# PCB-BC-BI.net
KiCad netlist of a schematic drawn in EAGLE
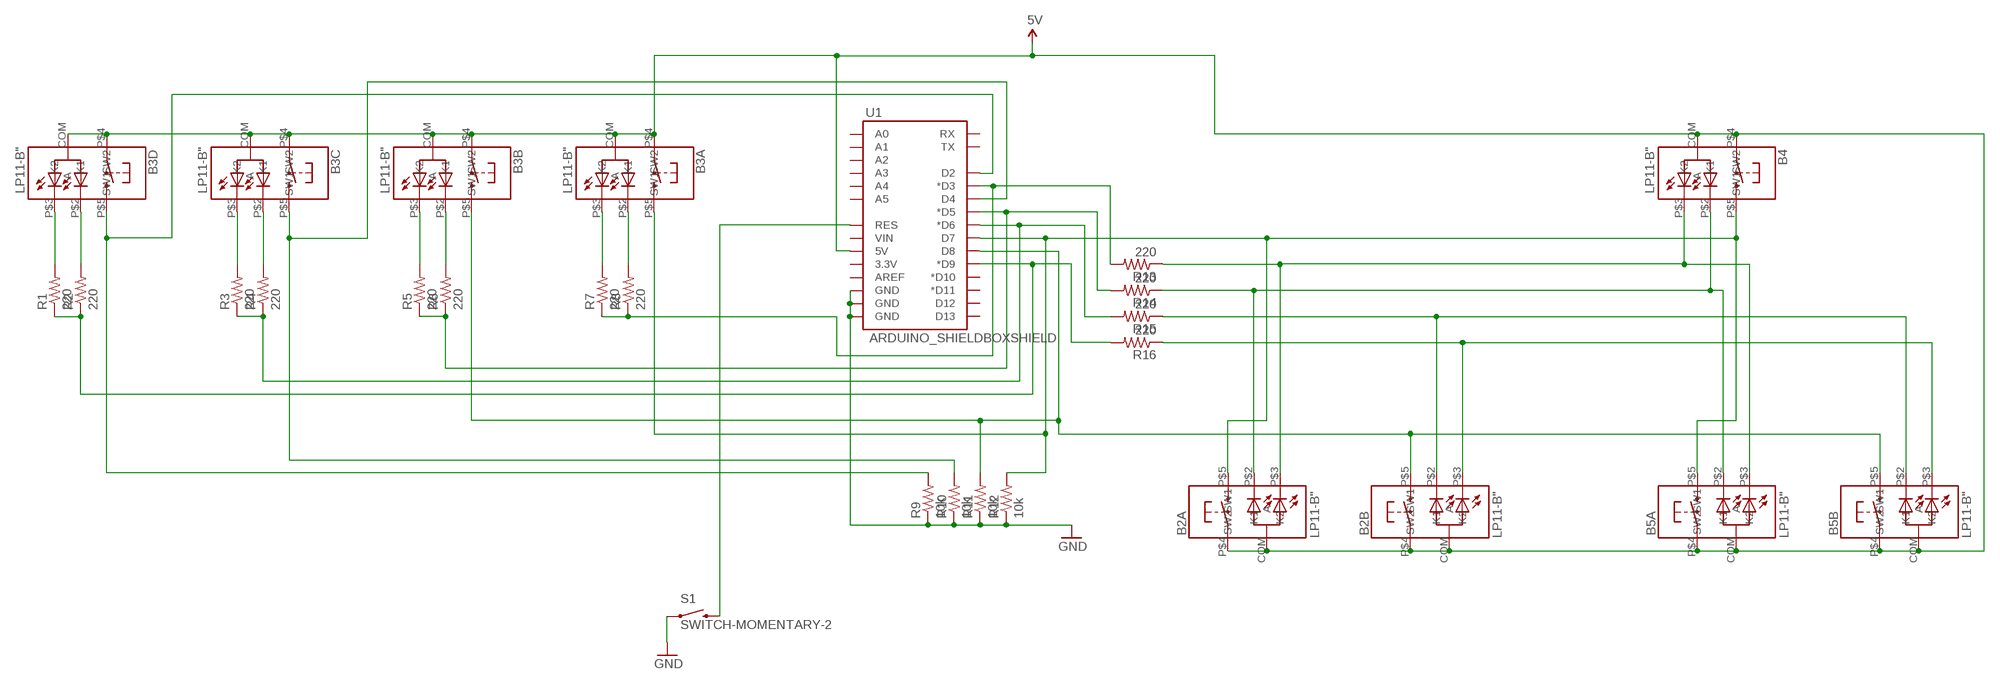
[diagram p0: schematic, sheet 1]

(export (version "E")
  (design (tool "Eeschema 10.0.6"))
  (components
    (comp (ref "B2A")
      (value "LP11-B\"")
      (footprint "eagle-import:LP11")
      (libsource (lib "eagle-import") (part "LP11-B{dblquote}"))
    )
    (comp (ref "B2B")
      (value "LP11-B\"")
      (footprint "eagle-import:LP11")
      (libsource (lib "eagle-import") (part "LP11-B{dblquote}"))
    )
    (comp (ref "B3A")
      (value "LP11-B\"")
      (footprint "eagle-import:LP11")
      (libsource (lib "eagle-import") (part "LP11-B{dblquote}"))
    )
    (comp (ref "B3B")
      (value "LP11-B\"")
      (footprint "eagle-import:LP11")
      (libsource (lib "eagle-import") (part "LP11-B{dblquote}"))
    )
    (comp (ref "B3C")
      (value "LP11-B\"")
      (footprint "eagle-import:LP11")
      (libsource (lib "eagle-import") (part "LP11-B{dblquote}"))
    )
    (comp (ref "B3D")
      (value "LP11-B\"")
      (footprint "eagle-import:LP11")
      (libsource (lib "eagle-import") (part "LP11-B{dblquote}"))
    )
    (comp (ref "B4")
      (value "LP11-B\"")
      (footprint "eagle-import:LP11")
      (libsource (lib "eagle-import") (part "LP11-B{dblquote}"))
    )
    (comp (ref "B5A")
      (value "LP11-B\"")
      (footprint "eagle-import:LP11")
      (libsource (lib "eagle-import") (part "LP11-B{dblquote}"))
    )
    (comp (ref "B5B")
      (value "LP11-B\"")
      (footprint "eagle-import:LP11")
      (libsource (lib "eagle-import") (part "LP11-B{dblquote}"))
    )
    (comp (ref "R1")
      (value "220")
      (footprint "eagle-import:0603-RES")
      (libsource (lib "eagle-import") (part "RESISTOR0603-RES"))
    )
    (comp (ref "R2")
      (value "220")
      (footprint "eagle-import:0603-RES")
      (libsource (lib "eagle-import") (part "RESISTOR0603-RES"))
    )
    (comp (ref "R3")
      (value "220")
      (footprint "eagle-import:0603-RES")
      (libsource (lib "eagle-import") (part "RESISTOR0603-RES"))
    )
    (comp (ref "R4")
      (value "220")
      (footprint "eagle-import:0603-RES")
      (libsource (lib "eagle-import") (part "RESISTOR0603-RES"))
    )
    (comp (ref "R5")
      (value "220")
      (footprint "eagle-import:0603-RES")
      (libsource (lib "eagle-import") (part "RESISTOR0603-RES"))
    )
    (comp (ref "R6")
      (value "220")
      (footprint "eagle-import:0603-RES")
      (libsource (lib "eagle-import") (part "RESISTOR0603-RES"))
    )
    (comp (ref "R7")
      (value "220")
      (footprint "eagle-import:0603-RES")
      (libsource (lib "eagle-import") (part "RESISTOR0603-RES"))
    )
    (comp (ref "R8")
      (value "220")
      (footprint "eagle-import:0603-RES")
      (libsource (lib "eagle-import") (part "RESISTOR0603-RES"))
    )
    (comp (ref "R9")
      (value "10k")
      (footprint "eagle-import:0603-RES")
      (libsource (lib "eagle-import") (part "RESISTOR0603-RES"))
    )
    (comp (ref "R10")
      (value "10k")
      (footprint "eagle-import:0603-RES")
      (libsource (lib "eagle-import") (part "RESISTOR0603-RES"))
    )
    (comp (ref "R11")
      (value "10k")
      (footprint "eagle-import:0603-RES")
      (libsource (lib "eagle-import") (part "RESISTOR0603-RES"))
    )
    (comp (ref "R12")
      (value "10k")
      (footprint "eagle-import:0603-RES")
      (libsource (lib "eagle-import") (part "RESISTOR0603-RES"))
    )
    (comp (ref "R13")
      (value "220")
      (footprint "eagle-import:0603-RES")
      (libsource (lib "eagle-import") (part "RESISTOR0603-RES"))
    )
    (comp (ref "R14")
      (value "220")
      (footprint "eagle-import:0603-RES")
      (libsource (lib "eagle-import") (part "RESISTOR0603-RES"))
    )
    (comp (ref "R15")
      (value "220")
      (footprint "eagle-import:0603-RES")
      (libsource (lib "eagle-import") (part "RESISTOR0603-RES"))
    )
    (comp (ref "R16")
      (value "220")
      (footprint "eagle-import:0603-RES")
      (libsource (lib "eagle-import") (part "RESISTOR0603-RES"))
    )
    (comp (ref "S1")
      (value "SWITCH-MOMENTARY-2")
      (footprint "eagle-import:TACTILE_SWITCH_TALL")
      (libsource (lib "eagle-import") (part "SWITCH-MOMENTARY-2"))
    )
    (comp (ref "U1")
      (value "ARDUINO_SHIELDBOXSHIELD")
      (footprint "eagle-import:ARDUINO_BOXSHIELD")
      (libsource (lib "eagle-import") (part "ARDUINO_SHIELDBOXSHIELD"))
    )
  )
  (nets
    (net (code "1") (name "5V") (class "Default")
      (node (ref "B2A") (pin "COM") (pinfunction "A_COM") (pintype "bidirectional"))
      (node (ref "B2A") (pin "P$4") (pinfunction "SW1_P$4") (pintype "bidirectional"))
      (node (ref "B2B") (pin "COM") (pinfunction "A_COM") (pintype "bidirectional"))
      (node (ref "B2B") (pin "P$4") (pinfunction "SW1_P$4") (pintype "bidirectional"))
      (node (ref "B3A") (pin "COM") (pinfunction "A_COM") (pintype "bidirectional"))
      (node (ref "B3A") (pin "P$4") (pinfunction "SW1_P$4") (pintype "bidirectional"))
      (node (ref "B3B") (pin "COM") (pinfunction "A_COM") (pintype "bidirectional"))
      (node (ref "B3B") (pin "P$4") (pinfunction "SW1_P$4") (pintype "bidirectional"))
      (node (ref "B3C") (pin "COM") (pinfunction "A_COM") (pintype "bidirectional"))
      (node (ref "B3C") (pin "P$4") (pinfunction "SW1_P$4") (pintype "bidirectional"))
      (node (ref "B3D") (pin "COM") (pinfunction "A_COM") (pintype "bidirectional"))
      (node (ref "B3D") (pin "P$4") (pinfunction "SW1_P$4") (pintype "bidirectional"))
      (node (ref "B4") (pin "COM") (pinfunction "A_COM") (pintype "bidirectional"))
      (node (ref "B4") (pin "P$4") (pinfunction "SW1_P$4") (pintype "bidirectional"))
      (node (ref "B5A") (pin "COM") (pinfunction "A_COM") (pintype "bidirectional"))
      (node (ref "B5A") (pin "P$4") (pinfunction "SW1_P$4") (pintype "bidirectional"))
      (node (ref "B5B") (pin "COM") (pinfunction "A_COM") (pintype "bidirectional"))
      (node (ref "B5B") (pin "P$4") (pinfunction "SW1_P$4") (pintype "bidirectional"))
      (node (ref "U1") (pin "5V@0") (pinfunction "5V_5V@0") (pintype "bidirectional"))
    )
    (net (code "2") (name "GND") (class "Default")
      (node (ref "R10") (pin "1") (pinfunction "1_1") (pintype "passive"))
      (node (ref "R11") (pin "1") (pinfunction "1_1") (pintype "passive"))
      (node (ref "R12") (pin "1") (pinfunction "1_1") (pintype "passive"))
      (node (ref "R9") (pin "1") (pinfunction "1_1") (pintype "passive"))
      (node (ref "S1") (pin "A2") (pinfunction "1_A2") (pintype "passive"))
      (node (ref "U1") (pin "GND@0") (pinfunction "GND_GND@0") (pintype "bidirectional"))
      (node (ref "U1") (pin "GND@1") (pinfunction "GND_GND@1") (pintype "bidirectional"))
      (node (ref "U1") (pin "GND@4") (pinfunction "GND_GND@4") (pintype "bidirectional"))
    )
    (net (code "3") (name "Net-(B2A-K1)") (class "Default")
      (node (ref "B2A") (pin "P$2") (pinfunction "K1_P$2") (pintype "bidirectional"))
      (node (ref "B4") (pin "P$2") (pinfunction "K1_P$2") (pintype "bidirectional"))
      (node (ref "B5A") (pin "P$2") (pinfunction "K1_P$2") (pintype "bidirectional"))
      (node (ref "R14") (pin "1") (pinfunction "1_1") (pintype "passive"))
    )
    (net (code "4") (name "Net-(B2A-K2)") (class "Default")
      (node (ref "B2A") (pin "P$3") (pinfunction "K2_P$3") (pintype "bidirectional"))
      (node (ref "B4") (pin "P$3") (pinfunction "K2_P$3") (pintype "bidirectional"))
      (node (ref "B5A") (pin "P$3") (pinfunction "K2_P$3") (pintype "bidirectional"))
      (node (ref "R13") (pin "1") (pinfunction "1_1") (pintype "passive"))
    )
    (net (code "5") (name "Net-(B2A-SW2)") (class "Default")
      (node (ref "B2A") (pin "P$5") (pinfunction "SW2_P$5") (pintype "bidirectional"))
      (node (ref "B3A") (pin "P$5") (pinfunction "SW2_P$5") (pintype "bidirectional"))
      (node (ref "B4") (pin "P$5") (pinfunction "SW2_P$5") (pintype "bidirectional"))
      (node (ref "B5A") (pin "P$5") (pinfunction "SW2_P$5") (pintype "bidirectional"))
      (node (ref "R12") (pin "2") (pinfunction "2_2") (pintype "passive"))
      (node (ref "U1") (pin "7") (pinfunction "D7_7") (pintype "bidirectional"))
    )
    (net (code "6") (name "Net-(B2B-K1)") (class "Default")
      (node (ref "B2B") (pin "P$2") (pinfunction "K1_P$2") (pintype "bidirectional"))
      (node (ref "B5B") (pin "P$2") (pinfunction "K1_P$2") (pintype "bidirectional"))
      (node (ref "R15") (pin "1") (pinfunction "1_1") (pintype "passive"))
    )
    (net (code "7") (name "Net-(B2B-K2)") (class "Default")
      (node (ref "B2B") (pin "P$3") (pinfunction "K2_P$3") (pintype "bidirectional"))
      (node (ref "B5B") (pin "P$3") (pinfunction "K2_P$3") (pintype "bidirectional"))
      (node (ref "R16") (pin "1") (pinfunction "1_1") (pintype "passive"))
    )
    (net (code "8") (name "Net-(B2B-SW2)") (class "Default")
      (node (ref "B2B") (pin "P$5") (pinfunction "SW2_P$5") (pintype "bidirectional"))
      (node (ref "B3B") (pin "P$5") (pinfunction "SW2_P$5") (pintype "bidirectional"))
      (node (ref "B5B") (pin "P$5") (pinfunction "SW2_P$5") (pintype "bidirectional"))
      (node (ref "R11") (pin "2") (pinfunction "2_2") (pintype "passive"))
      (node (ref "U1") (pin "8") (pinfunction "D8_8") (pintype "bidirectional"))
    )
    (net (code "9") (name "Net-(B3A-K1)") (class "Default")
      (node (ref "B3A") (pin "P$2") (pinfunction "K1_P$2") (pintype "bidirectional"))
      (node (ref "R8") (pin "2") (pinfunction "2_2") (pintype "passive"))
    )
    (net (code "10") (name "Net-(B3A-K2)") (class "Default")
      (node (ref "B3A") (pin "P$3") (pinfunction "K2_P$3") (pintype "bidirectional"))
      (node (ref "R7") (pin "2") (pinfunction "2_2") (pintype "passive"))
    )
    (net (code "11") (name "Net-(B3B-K1)") (class "Default")
      (node (ref "B3B") (pin "P$2") (pinfunction "K1_P$2") (pintype "bidirectional"))
      (node (ref "R6") (pin "2") (pinfunction "2_2") (pintype "passive"))
    )
    (net (code "12") (name "Net-(B3B-K2)") (class "Default")
      (node (ref "B3B") (pin "P$3") (pinfunction "K2_P$3") (pintype "bidirectional"))
      (node (ref "R5") (pin "2") (pinfunction "2_2") (pintype "passive"))
    )
    (net (code "13") (name "Net-(B3C-K1)") (class "Default")
      (node (ref "B3C") (pin "P$2") (pinfunction "K1_P$2") (pintype "bidirectional"))
      (node (ref "R4") (pin "2") (pinfunction "2_2") (pintype "passive"))
    )
    (net (code "14") (name "Net-(B3C-K2)") (class "Default")
      (node (ref "B3C") (pin "P$3") (pinfunction "K2_P$3") (pintype "bidirectional"))
      (node (ref "R3") (pin "2") (pinfunction "2_2") (pintype "passive"))
    )
    (net (code "15") (name "Net-(B3C-SW2)") (class "Default")
      (node (ref "B3C") (pin "P$5") (pinfunction "SW2_P$5") (pintype "bidirectional"))
      (node (ref "R10") (pin "2") (pinfunction "2_2") (pintype "passive"))
      (node (ref "U1") (pin "4") (pinfunction "D4_4") (pintype "bidirectional"))
    )
    (net (code "16") (name "Net-(B3D-K1)") (class "Default")
      (node (ref "B3D") (pin "P$2") (pinfunction "K1_P$2") (pintype "bidirectional"))
      (node (ref "R2") (pin "2") (pinfunction "2_2") (pintype "passive"))
    )
    (net (code "17") (name "Net-(B3D-K2)") (class "Default")
      (node (ref "B3D") (pin "P$3") (pinfunction "K2_P$3") (pintype "bidirectional"))
      (node (ref "R1") (pin "2") (pinfunction "2_2") (pintype "passive"))
    )
    (net (code "18") (name "Net-(B3D-SW2)") (class "Default")
      (node (ref "B3D") (pin "P$5") (pinfunction "SW2_P$5") (pintype "bidirectional"))
      (node (ref "R9") (pin "2") (pinfunction "2_2") (pintype "passive"))
      (node (ref "U1") (pin "2") (pinfunction "D2_2") (pintype "bidirectional"))
    )
    (net (code "19") (name "Net-(S1-2)") (class "Default")
      (node (ref "S1") (pin "B2") (pinfunction "2_B2") (pintype "passive"))
      (node (ref "U1") (pin "RESET") (pinfunction "RES_RESET") (pintype "bidirectional"))
    )
    (net (code "20") (name "Net-(U1-*D3)") (class "Default")
      (node (ref "R13") (pin "2") (pinfunction "2_2") (pintype "passive"))
      (node (ref "R7") (pin "1") (pinfunction "1_1") (pintype "passive"))
      (node (ref "R8") (pin "1") (pinfunction "1_1") (pintype "passive"))
      (node (ref "U1") (pin "3") (pinfunction "*D3_3") (pintype "bidirectional"))
    )
    (net (code "21") (name "Net-(U1-*D5)") (class "Default")
      (node (ref "R14") (pin "2") (pinfunction "2_2") (pintype "passive"))
      (node (ref "R5") (pin "1") (pinfunction "1_1") (pintype "passive"))
      (node (ref "R6") (pin "1") (pinfunction "1_1") (pintype "passive"))
      (node (ref "U1") (pin "5") (pinfunction "*D5_5") (pintype "bidirectional"))
    )
    (net (code "22") (name "Net-(U1-*D6)") (class "Default")
      (node (ref "R15") (pin "2") (pinfunction "2_2") (pintype "passive"))
      (node (ref "R3") (pin "1") (pinfunction "1_1") (pintype "passive"))
      (node (ref "R4") (pin "1") (pinfunction "1_1") (pintype "passive"))
      (node (ref "U1") (pin "6") (pinfunction "*D6_6") (pintype "bidirectional"))
    )
    (net (code "23") (name "Net-(U1-*D9)") (class "Default")
      (node (ref "R1") (pin "1") (pinfunction "1_1") (pintype "passive"))
      (node (ref "R16") (pin "2") (pinfunction "2_2") (pintype "passive"))
      (node (ref "R2") (pin "1") (pinfunction "1_1") (pintype "passive"))
      (node (ref "U1") (pin "9") (pinfunction "*D9_9") (pintype "bidirectional"))
    )
    (net (code "24") (name "unconnected-(U1-*D10-Pad10)") (class "Default")
      (node (ref "U1") (pin "10") (pinfunction "*D10_10") (pintype "bidirectional"))
    )
    (net (code "25") (name "unconnected-(U1-*D11-Pad11)") (class "Default")
      (node (ref "U1") (pin "11") (pinfunction "*D11_11") (pintype "bidirectional"))
    )
    (net (code "26") (name "unconnected-(U1-D12-Pad12)") (class "Default")
      (node (ref "U1") (pin "12") (pinfunction "D12_12") (pintype "bidirectional"))
    )
    (net (code "27") (name "unconnected-(U1-D13-Pad13)") (class "Default")
      (node (ref "U1") (pin "13") (pinfunction "D13_13") (pintype "bidirectional"))
    )
    (net (code "28") (name "unconnected-(U1-Pad3.3V)") (class "Default")
      (node (ref "U1") (pin "3.3V") (pinfunction "3.3V_3.3V") (pintype "bidirectional"))
    )
    (net (code "29") (name "unconnected-(U1-PadA0)") (class "Default")
      (node (ref "U1") (pin "A0") (pinfunction "A0_A0") (pintype "bidirectional"))
    )
    (net (code "30") (name "unconnected-(U1-PadA1)") (class "Default")
      (node (ref "U1") (pin "A1") (pinfunction "A1_A1") (pintype "bidirectional"))
    )
    (net (code "31") (name "unconnected-(U1-PadA2)") (class "Default")
      (node (ref "U1") (pin "A2") (pinfunction "A2_A2") (pintype "bidirectional"))
    )
    (net (code "32") (name "unconnected-(U1-PadA3)") (class "Default")
      (node (ref "U1") (pin "A3") (pinfunction "A3_A3") (pintype "bidirectional"))
    )
    (net (code "33") (name "unconnected-(U1-PadA4)") (class "Default")
      (node (ref "U1") (pin "A4") (pinfunction "A4_A4") (pintype "bidirectional"))
    )
    (net (code "34") (name "unconnected-(U1-PadA5)") (class "Default")
      (node (ref "U1") (pin "A5") (pinfunction "A5_A5") (pintype "bidirectional"))
    )
    (net (code "35") (name "unconnected-(U1-PadAREF)") (class "Default")
      (node (ref "U1") (pin "AREF") (pinfunction "AREF_AREF") (pintype "bidirectional"))
    )
    (net (code "36") (name "unconnected-(U1-PadVIN)") (class "Default")
      (node (ref "U1") (pin "VIN") (pinfunction "VIN_VIN") (pintype "bidirectional"))
    )
    (net (code "37") (name "unconnected-(U1-RX-Pad0)") (class "Default")
      (node (ref "U1") (pin "0") (pinfunction "RX_0") (pintype "bidirectional"))
    )
    (net (code "38") (name "unconnected-(U1-TX-Pad1)") (class "Default")
      (node (ref "U1") (pin "1") (pinfunction "TX_1") (pintype "bidirectional"))
    )
  )
)
